# Power.net
KiCad netlist of a schematic drawn in Altium Designer
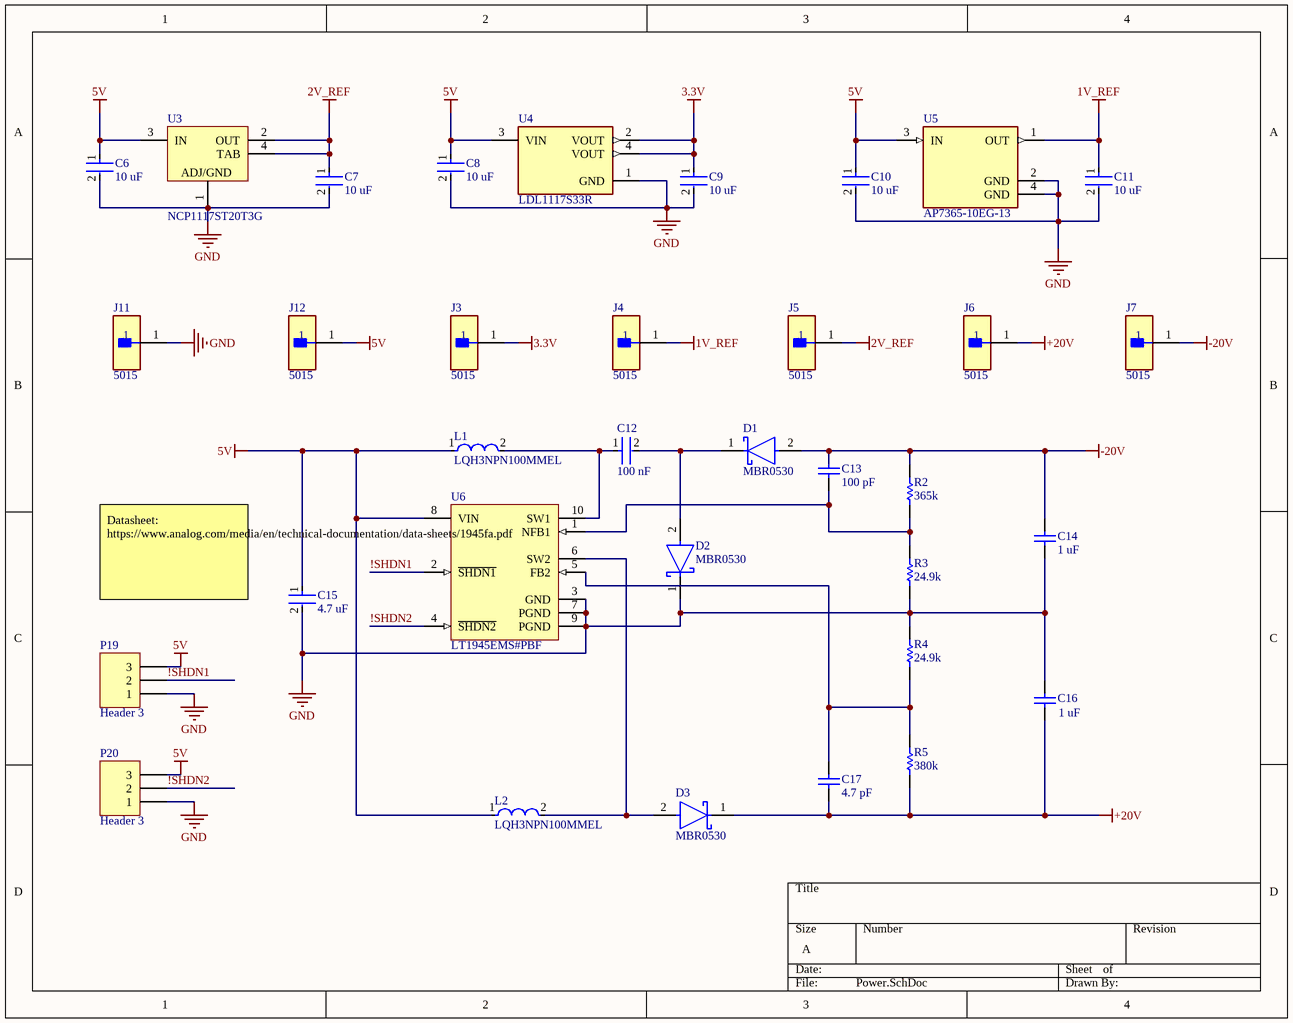
[diagram p0: Power.SchDoc]

(export (version "E")
  (design (tool "Eeschema 10.0.6"))
  (components
    (comp (ref "C6")
      (value "10 uF")
      (footprint "FP-CL21-IPC_A")
      (description "CL21 Series 0805 10uF 25V ±10% Tolerance X5R Multilayer Ceramic Chip Capacitor")
      (fields (field (name "TOLERANCE") "10%"))
      (libsource (lib "Altium Content Vault") (part "b4654b650e69147ec39a6b967a45e02"))
    )
    (comp (ref "C7")
      (value "10 uF")
      (footprint "FP-CL21-IPC_A")
      (description "CL21 Series 0805 10uF 25V ±10% Tolerance X5R Multilayer Ceramic Chip Capacitor")
      (fields (field (name "TOLERANCE") "10%"))
      (libsource (lib "Altium Content Vault") (part "b4654b650e69147ec39a6b967a45e02"))
    )
    (comp (ref "C8")
      (value "10 uF")
      (footprint "FP-CL21-IPC_A")
      (description "CL21 Series 0805 10uF 25V ±10% Tolerance X5R Multilayer Ceramic Chip Capacitor")
      (fields (field (name "TOLERANCE") "10%"))
      (libsource (lib "Altium Content Vault") (part "b4654b650e69147ec39a6b967a45e02"))
    )
    (comp (ref "C9")
      (value "10 uF")
      (footprint "FP-CL21-IPC_A")
      (description "CL21 Series 0805 10uF 25V ±10% Tolerance X5R Multilayer Ceramic Chip Capacitor")
      (fields (field (name "TOLERANCE") "10%"))
      (libsource (lib "Altium Content Vault") (part "b4654b650e69147ec39a6b967a45e02"))
    )
    (comp (ref "C10")
      (value "10 uF")
      (footprint "FP-CL21-IPC_A")
      (description "CL21 Series 0805 10uF 25V ±10% Tolerance X5R Multilayer Ceramic Chip Capacitor")
      (fields (field (name "TOLERANCE") "10%"))
      (libsource (lib "Altium Content Vault") (part "b4654b650e69147ec39a6b967a45e02"))
    )
    (comp (ref "C11")
      (value "10 uF")
      (footprint "FP-CL21-IPC_A")
      (description "CL21 Series 0805 10uF 25V ±10% Tolerance X5R Multilayer Ceramic Chip Capacitor")
      (fields (field (name "TOLERANCE") "10%"))
      (libsource (lib "Altium Content Vault") (part "b4654b650e69147ec39a6b967a45e02"))
    )
    (comp (ref "C12")
      (value "100 nF")
      (footprint "FP-C0805C-DN-MFG")
      (description "CAP CER 0.1UF 50V X7R 0805")
      (fields
        (field (name "MANUFACTURER PART NUMBER") "C0805C104K5RACTU")
        (field (name "MANUFACTURER") "KEMET")
      )
      (libsource (lib "Altium Content Vault") (part "b4654b650e69147ec39a6b967a45e02"))
    )
    (comp (ref "C13")
      (value "100 pF")
      (footprint "CAPC2013X140X50ML20T25")
      (description "08055C101KAT2A")
      (fields (field (name "MANUFACTURER") "AVX Interconnect / Elco"))
      (libsource (lib "Altium Content Vault") (part "CAP"))
    )
    (comp (ref "C14")
      (value "1 uF")
      (footprint "CAPC3216X110X50LL20T25")
      (description "C1206C105K5RACTU")
      (fields (field (name "MANUFACTURER") "Kemet") (field (name "TOLERANCE") "10%"))
      (libsource (lib "Altium Content Vault") (part "CAP-NP-2"))
    )
    (comp (ref "C15")
      (value "4.7 uF")
      (footprint "FP-C0805C475K3PACTU-MFG")
      (description "CAP CER 4.7UF 25V X5R 0805")
      (fields (field (name "TOLERANCE") "10%") (field (name "VOLTAGE") "25V"))
      (libsource (lib "Altium Content Vault") (part "02cd4be3c70576c341d710602a673aa"))
    )
    (comp (ref "C16")
      (value "1 uF")
      (footprint "CAPC3216X110X50LL20T25")
      (description "C1206C105K5RACTU")
      (fields (field (name "MANUFACTURER") "Kemet") (field (name "TOLERANCE") "10%"))
      (libsource (lib "Altium Content Vault") (part "CAP-NP-2"))
    )
    (comp (ref "C17")
      (value "4.7 pF")
      (footprint "CAPC2013X71X50ML20T25")
      (description "08055A4R7CAT2A")
      (fields (field (name "MANUFACTURER") "AVX Interconnect / Elco"))
      (libsource (lib "Altium Content Vault") (part "CAP"))
    )
    (comp (ref "D1")
      (value "MBR0530")
      (footprint "FP-425-04-MFG")
      (description "DIODE SCHOTTKY 30V 500MA SOD123")
      (libsource (lib "Altium Content Vault") (part "1d6ec82d83fb6aee721767c19dac4b9"))
    )
    (comp (ref "D2")
      (value "MBR0530")
      (footprint "FP-425-04-MFG")
      (description "DIODE SCHOTTKY 30V 500MA SOD123")
      (libsource (lib "Altium Content Vault") (part "1d6ec82d83fb6aee721767c19dac4b9"))
    )
    (comp (ref "D3")
      (value "MBR0530")
      (footprint "FP-425-04-MFG")
      (description "DIODE SCHOTTKY 30V 500MA SOD123")
      (libsource (lib "Altium Content Vault") (part "1d6ec82d83fb6aee721767c19dac4b9"))
    )
    (comp (ref "J3")
      (value "5015")
      (footprint "FP-5015-MFG")
      (description "PC TEST POINT MINIATURE")
      (fields
        (field (name "MANUFACTURER") "keystone")
        (field (name "OCTOPART") "https://octopart.com/5015-keystone-3822")
      )
      (libsource (lib "Altium Content Vault") (part "dd45045ce8184df9e99e12baf3f412c"))
    )
    (comp (ref "J4")
      (value "5015")
      (footprint "FP-5015-MFG")
      (description "PC TEST POINT MINIATURE")
      (fields
        (field (name "MANUFACTURER") "keystone")
        (field (name "OCTOPART") "https://octopart.com/5015-keystone-3822")
      )
      (libsource (lib "Altium Content Vault") (part "dd45045ce8184df9e99e12baf3f412c"))
    )
    (comp (ref "J5")
      (value "5015")
      (footprint "FP-5015-MFG")
      (description "PC TEST POINT MINIATURE")
      (fields
        (field (name "MANUFACTURER") "keystone")
        (field (name "OCTOPART") "https://octopart.com/5015-keystone-3822")
      )
      (libsource (lib "Altium Content Vault") (part "dd45045ce8184df9e99e12baf3f412c"))
    )
    (comp (ref "J6")
      (value "5015")
      (footprint "FP-5015-MFG")
      (description "PC TEST POINT MINIATURE")
      (fields
        (field (name "MANUFACTURER") "keystone")
        (field (name "OCTOPART") "https://octopart.com/5015-keystone-3822")
      )
      (libsource (lib "Altium Content Vault") (part "dd45045ce8184df9e99e12baf3f412c"))
    )
    (comp (ref "J7")
      (value "5015")
      (footprint "FP-5015-MFG")
      (description "PC TEST POINT MINIATURE")
      (fields
        (field (name "MANUFACTURER") "keystone")
        (field (name "OCTOPART") "https://octopart.com/5015-keystone-3822")
      )
      (libsource (lib "Altium Content Vault") (part "dd45045ce8184df9e99e12baf3f412c"))
    )
    (comp (ref "J11")
      (value "5015")
      (footprint "FP-5015-MFG")
      (description "PC TEST POINT MINIATURE")
      (fields
        (field (name "MANUFACTURER") "keystone")
        (field (name "OCTOPART") "https://octopart.com/5015-keystone-3822")
      )
      (libsource (lib "Altium Content Vault") (part "dd45045ce8184df9e99e12baf3f412c"))
    )
    (comp (ref "J12")
      (value "5015")
      (footprint "FP-5015-MFG")
      (description "PC TEST POINT MINIATURE")
      (fields
        (field (name "MANUFACTURER") "keystone")
        (field (name "OCTOPART") "https://octopart.com/5015-keystone-3822")
      )
      (libsource (lib "Altium Content Vault") (part "dd45045ce8184df9e99e12baf3f412c"))
    )
    (comp (ref "L1")
      (value "LQH3NPN100MMEL")
      (footprint "FP-LQH3NPH_ME-MFG")
      (description "Wire Wound Ferrite Inductor for Power Lines 10μH ±20% 0.228Ω 1280mA 1212")
      (fields (field (name "TOLERANCE") "20%"))
      (libsource (lib "Altium Content Vault") (part "725321dda6339637d4d059423bc1c3c"))
    )
    (comp (ref "L2")
      (value "LQH3NPN100MMEL")
      (footprint "FP-LQH3NPH_ME-MFG")
      (description "Wire Wound Ferrite Inductor for Power Lines 10μH ±20% 0.228Ω 1280mA 1212")
      (fields (field (name "TOLERANCE") "20%"))
      (libsource (lib "Altium Content Vault") (part "725321dda6339637d4d059423bc1c3c"))
    )
    (comp (ref "P19")
      (value "Header 3")
      (footprint "HDR1X3")
      (description "Header, 3-Pin")
      (fields (field (name "PUBLISHER") "Altium Limited"))
      (libsource (lib "Miscellaneous Connectors") (part "Header 3"))
    )
    (comp (ref "P20")
      (value "Header 3")
      (footprint "HDR1X3")
      (description "Header, 3-Pin")
      (fields (field (name "PUBLISHER") "Altium Limited"))
      (libsource (lib "Miscellaneous Connectors") (part "Header 3"))
    )
    (comp (ref "R2")
      (value "365k")
      (footprint "RESC2013X70X40NL20T20")
      (fields (field (name "PART NUMBER") "ERJ-6ENF3653V") (field (name "MANUFACTURER") "Panasonic"))
      (libsource (lib "Altium Content Vault") (part "RES"))
    )
    (comp (ref "R3")
      (value "24.9k")
      (footprint "RESC2013X70X40LL20T20")
      (fields (field (name "PART NUMBER") "ERJ-6ENF2492V") (field (name "MANUFACTURER") "Panasonic"))
      (libsource (lib "Altium Content Vault") (part "RES"))
    )
    (comp (ref "R4")
      (value "24.9k")
      (footprint "RESC2013X70X40LL20T20")
      (fields (field (name "PART NUMBER") "ERJ-6ENF2492V") (field (name "MANUFACTURER") "Panasonic"))
      (libsource (lib "Altium Content Vault") (part "RES"))
    )
    (comp (ref "R5")
      (value "380k")
      (footprint "RESC2013X70X40ML20T20")
      (fields (field (name "PART NUMBER") "ERJ-6ENF3833V") (field (name "MANUFACTURER") "Panasonic"))
      (libsource (lib "Altium Content Vault") (part "RES"))
    )
    (comp (ref "U3")
      (value "NCP1117ST20T3G")
      (footprint "ONSC-SOT-223-4-318H-01_A_V")
      (fields (field (name "TOLERANCE") "1%"))
      (libsource (lib "Altium Content Vault") (part "ONSC-NCP1117-SOT223-4"))
    )
    (comp (ref "U4")
      (value "LDL1117S33R")
      (footprint "FP-SOT223-0046067-IPC_C")
      (description "IC REG LINEAR 3.3V 1.2A SOT223")
      (fields
        (field (name "OCTOPART") "https://octopart.com/ldl1117s33r-stmicroelectronics-81876163")
        (field (name "MANUFACTURER") "STMicroelectronics")
      )
      (libsource (lib "Altium Content Vault") (part "a602d55cb6d43002de8a72f1c695f0a"))
    )
    (comp (ref "U5")
      (value "AP7365-10EG-13")
      (footprint "FP-SOT223-IPC_C")
      (description "IC REG LIN 1V 600MA SOT223-3")
      (libsource (lib "Altium Content Vault") (part "76d57bcc2558094fcdb354c83fb3a1f"))
    )
    (comp (ref "U6")
      (value "LT1945EMS#PBF")
      (footprint "LT-MS-10_N")
      (fields (field (name "MANUFACTURER") "Linear Technology"))
      (libsource (lib "Altium Content Vault") (part "LT-LT1945-MS-10"))
    )
  )
  (nets
    (net (code "1") (name "+20V") (class "Default")
      (node (ref "C16") (pin "1") (pinfunction "1_1") (pintype "passive"))
      (node (ref "C17") (pin "1") (pinfunction "1_1") (pintype "passive"))
      (node (ref "D3") (pin "1") (pinfunction "C_1") (pintype "passive"))
      (node (ref "J6") (pin "1") (pinfunction "1_1") (pintype "passive"))
      (node (ref "R5") (pin "1") (pinfunction "1_1") (pintype "passive"))
    )
    (net (code "2") (name "-20V") (class "Default")
      (node (ref "C13") (pin "1") (pinfunction "1_1") (pintype "passive"))
      (node (ref "C14") (pin "2") (pinfunction "2_2") (pintype "passive"))
      (node (ref "D1") (pin "2") (pinfunction "A_2") (pintype "passive"))
      (node (ref "J7") (pin "1") (pinfunction "1_1") (pintype "passive"))
      (node (ref "R2") (pin "2") (pinfunction "2_2") (pintype "passive"))
    )
    (net (code "3") (name "/!SHDN1") (class "Default")
      (node (ref "P19") (pin "2") (pinfunction "2_2") (pintype "passive"))
      (node (ref "U6") (pin "2") (pinfunction "~{SHDN1}_2") (pintype "input"))
    )
    (net (code "4") (name "/!SHDN2") (class "Default")
      (node (ref "P20") (pin "2") (pinfunction "2_2") (pintype "passive"))
      (node (ref "U6") (pin "4") (pinfunction "~{SHDN2}_4") (pintype "input"))
    )
    (net (code "5") (name "1V_REF") (class "Default")
      (node (ref "C11") (pin "1") (pinfunction "1_1") (pintype "passive"))
      (node (ref "J4") (pin "1") (pinfunction "1_1") (pintype "passive"))
      (node (ref "U5") (pin "1") (pinfunction "OUT_1") (pintype "output"))
    )
    (net (code "6") (name "2V_REF") (class "Default")
      (node (ref "C7") (pin "1") (pinfunction "1_1") (pintype "passive"))
      (node (ref "J5") (pin "1") (pinfunction "1_1") (pintype "passive"))
      (node (ref "U3") (pin "2") (pinfunction "OUT_2") (pintype "power_in"))
      (node (ref "U3") (pin "4") (pinfunction "TAB_4") (pintype "passive"))
    )
    (net (code "7") (name "3.3V") (class "Default")
      (node (ref "C9") (pin "1") (pinfunction "1_1") (pintype "passive"))
      (node (ref "J3") (pin "1") (pinfunction "1_1") (pintype "passive"))
      (node (ref "U4") (pin "2") (pinfunction "VOUT_2") (pintype "output"))
      (node (ref "U4") (pin "4") (pinfunction "VOUT_4") (pintype "output"))
    )
    (net (code "8") (name "5V") (class "Default")
      (node (ref "C10") (pin "1") (pinfunction "1_1") (pintype "passive"))
      (node (ref "C15") (pin "1") (pinfunction "1_1") (pintype "passive"))
      (node (ref "C6") (pin "1") (pinfunction "1_1") (pintype "passive"))
      (node (ref "C8") (pin "1") (pinfunction "1_1") (pintype "passive"))
      (node (ref "J12") (pin "1") (pinfunction "1_1") (pintype "passive"))
      (node (ref "L1") (pin "1") (pinfunction "1_1") (pintype "passive"))
      (node (ref "L2") (pin "1") (pinfunction "1_1") (pintype "passive"))
      (node (ref "P19") (pin "3") (pinfunction "3_3") (pintype "passive"))
      (node (ref "P20") (pin "3") (pinfunction "3_3") (pintype "passive"))
      (node (ref "U3") (pin "3") (pinfunction "IN_3") (pintype "power_in"))
      (node (ref "U4") (pin "3") (pinfunction "VIN_3") (pintype "power_in"))
      (node (ref "U5") (pin "3") (pinfunction "IN_3") (pintype "input"))
      (node (ref "U6") (pin "8") (pinfunction "VIN_8") (pintype "power_in"))
    )
    (net (code "9") (name "GND") (class "Default")
      (node (ref "C10") (pin "2") (pinfunction "2_2") (pintype "passive"))
      (node (ref "C11") (pin "2") (pinfunction "2_2") (pintype "passive"))
      (node (ref "C14") (pin "1") (pinfunction "1_1") (pintype "passive"))
      (node (ref "C15") (pin "2") (pinfunction "2_2") (pintype "passive"))
      (node (ref "C16") (pin "2") (pinfunction "2_2") (pintype "passive"))
      (node (ref "C6") (pin "2") (pinfunction "2_2") (pintype "passive"))
      (node (ref "C7") (pin "2") (pinfunction "2_2") (pintype "passive"))
      (node (ref "C8") (pin "2") (pinfunction "2_2") (pintype "passive"))
      (node (ref "C9") (pin "2") (pinfunction "2_2") (pintype "passive"))
      (node (ref "D2") (pin "1") (pinfunction "C_1") (pintype "passive"))
      (node (ref "J11") (pin "1") (pinfunction "1_1") (pintype "passive"))
      (node (ref "P19") (pin "1") (pinfunction "1_1") (pintype "passive"))
      (node (ref "P20") (pin "1") (pinfunction "1_1") (pintype "passive"))
      (node (ref "R3") (pin "1") (pinfunction "1_1") (pintype "passive"))
      (node (ref "R4") (pin "2") (pinfunction "2_2") (pintype "passive"))
      (node (ref "U3") (pin "1") (pinfunction "ADJ/GND_1") (pintype "passive"))
      (node (ref "U4") (pin "1") (pinfunction "GND_1") (pintype "power_in"))
      (node (ref "U5") (pin "2") (pinfunction "GND_2") (pintype "power_in"))
      (node (ref "U5") (pin "4") (pinfunction "GND_4") (pintype "power_in"))
      (node (ref "U6") (pin "3") (pinfunction "GND_3") (pintype "power_in"))
      (node (ref "U6") (pin "7") (pinfunction "PGND_7") (pintype "power_in"))
      (node (ref "U6") (pin "9") (pinfunction "PGND_9") (pintype "power_in"))
    )
    (net (code "10") (name "Net-(D1-C)") (class "Default")
      (node (ref "C12") (pin "2") (pinfunction "2_2") (pintype "passive"))
      (node (ref "D1") (pin "1") (pinfunction "C_1") (pintype "passive"))
      (node (ref "D2") (pin "2") (pinfunction "A_2") (pintype "passive"))
    )
    (net (code "11") (name "Net-(D3-A)") (class "Default")
      (node (ref "D3") (pin "2") (pinfunction "A_2") (pintype "passive"))
      (node (ref "L2") (pin "2") (pinfunction "2_2") (pintype "passive"))
      (node (ref "U6") (pin "6") (pinfunction "SW2_6") (pintype "power_in"))
    )
    (net (code "12") (name "Net-(U6-FB2)") (class "Default")
      (node (ref "C17") (pin "2") (pinfunction "2_2") (pintype "passive"))
      (node (ref "R4") (pin "1") (pinfunction "1_1") (pintype "passive"))
      (node (ref "R5") (pin "2") (pinfunction "2_2") (pintype "passive"))
      (node (ref "U6") (pin "5") (pinfunction "FB2_5") (pintype "input"))
    )
    (net (code "13") (name "Net-(U6-NFB1)") (class "Default")
      (node (ref "C13") (pin "2") (pinfunction "2_2") (pintype "passive"))
      (node (ref "R2") (pin "1") (pinfunction "1_1") (pintype "passive"))
      (node (ref "R3") (pin "2") (pinfunction "2_2") (pintype "passive"))
      (node (ref "U6") (pin "1") (pinfunction "NFB1_1") (pintype "input"))
    )
    (net (code "14") (name "Net-(U6-SW1)") (class "Default")
      (node (ref "C12") (pin "1") (pinfunction "1_1") (pintype "passive"))
      (node (ref "L1") (pin "2") (pinfunction "2_2") (pintype "passive"))
      (node (ref "U6") (pin "10") (pinfunction "SW1_10") (pintype "power_in"))
    )
  )
)
